# Power.net
KiCad netlist of a schematic drawn in Altium Designer
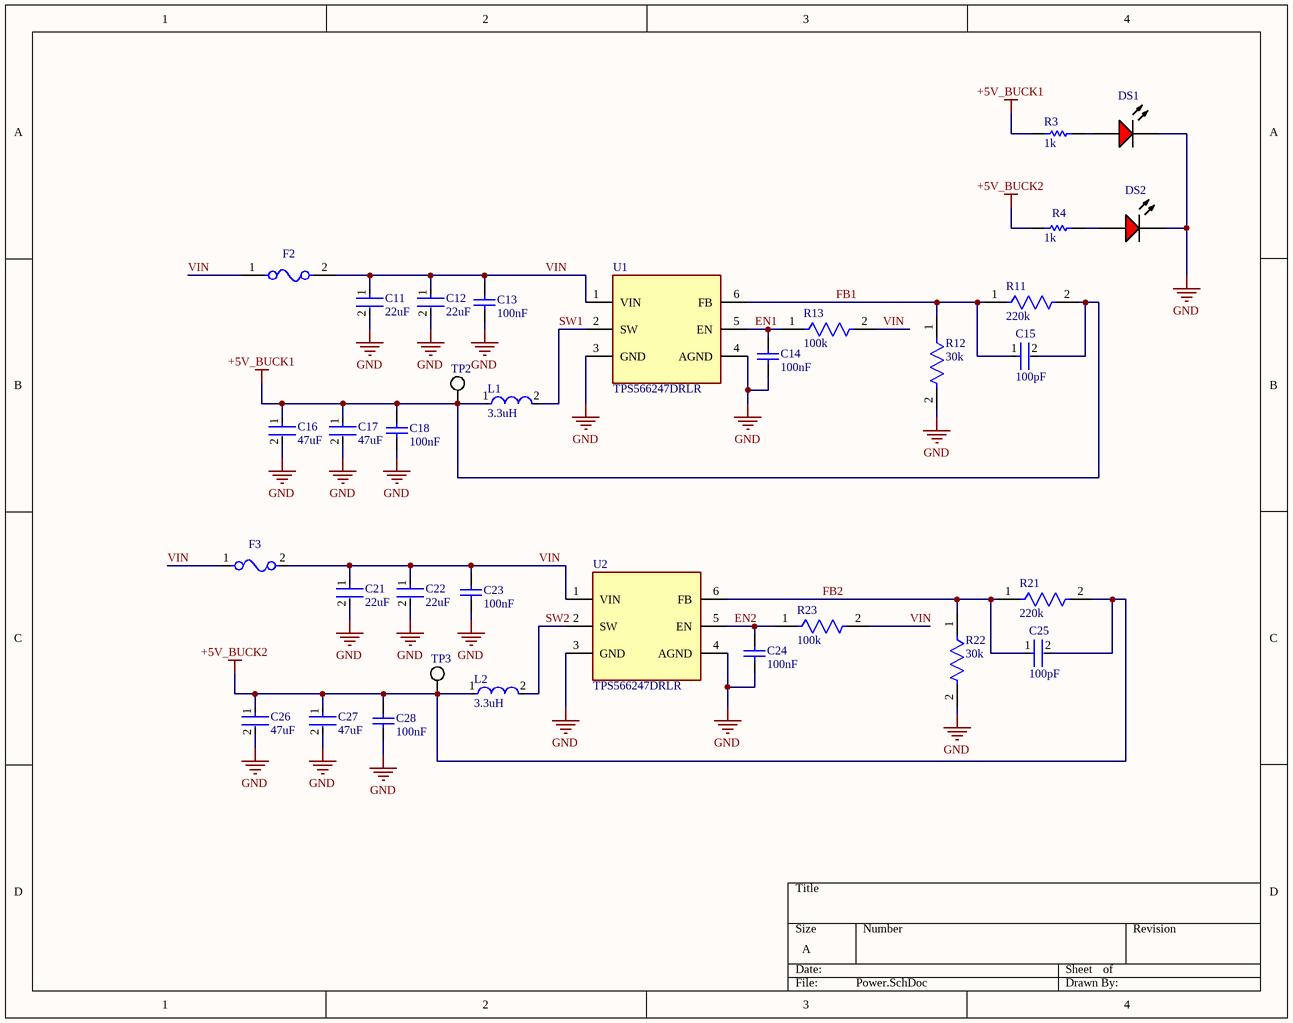
[diagram p0: Power.SchDoc]

(export (version "E")
  (design (tool "Eeschema 10.0.6"))
  (components
    (comp (ref "C11")
      (value "22uF")
      (footprint "FP-1206-L_3_2_0_3-W_1_6_0-IPC_A")
      (description "None")
      (fields (field (name "TOLERANCE") "20%"))
      (libsource (lib "Altium Content Vault") (part "11868f565c42a9108669ba33697ecf6"))
    )
    (comp (ref "C12")
      (value "22uF")
      (footprint "FP-1206-L_3_2_0_3-W_1_6_0-IPC_A")
      (description "None")
      (fields (field (name "TOLERANCE") "20%"))
      (libsource (lib "Altium Content Vault") (part "11868f565c42a9108669ba33697ecf6"))
    )
    (comp (ref "C13")
      (value "100nF")
      (footprint "CAPC1206(3216)170_L")
      (description "CAP 100nF 50V ±10% 1206 (3216 Metric) Thickness 1.7mm SMD")
      (fields (field (name "TOLERANCE") "Â±10%"))
      (libsource (lib "Altium Content Vault") (part "CAP"))
    )
    (comp (ref "C14")
      (value "100nF")
      (footprint "CAPC1206(3216)170_L")
      (description "CAP 100nF 50V ±10% 1206 (3216 Metric) Thickness 1.7mm SMD")
      (fields (field (name "TOLERANCE") "Â±10%"))
      (libsource (lib "Altium Content Vault") (part "CAP"))
    )
    (comp (ref "C15")
      (value "100pF")
      (footprint "FP-C0805C-DN-MFG")
      (description "CAP CER 100PF 50V 10% X7R 0805 (used for feed-forward)")
      (fields
        (field (name "OCTOPART") "https://octopart.com/c0805c101k5ractu-kemet-10441514")
        (field (name "MANUFACTURER") "KEMET")
      )
      (libsource (lib "Altium Content Vault") (part "b4654b650e69147ec39a6b967a45e02"))
    )
    (comp (ref "C16")
      (value "47uF")
      (footprint "FP-1210-L_3_2_0_3-W_2_5_0-IPC_B")
      (description "Capacitor Ceramic Multilayer 47uF 10% 10V X7R SMD 1210")
      (fields (field (name "TOLERANCE") "10%"))
      (libsource (lib "Altium Content Vault") (part "02cd4be3c70576c341d710602a673aa"))
    )
    (comp (ref "C17")
      (value "47uF")
      (footprint "FP-1210-L_3_2_0_3-W_2_5_0-IPC_B")
      (description "Capacitor Ceramic Multilayer 47uF 10% 10V X7R SMD 1210")
      (fields (field (name "TOLERANCE") "10%"))
      (libsource (lib "Altium Content Vault") (part "02cd4be3c70576c341d710602a673aa"))
    )
    (comp (ref "C18")
      (value "100nF")
      (footprint "CAPC1206(3216)170_L")
      (description "CAP 100nF 50V ±10% 1206 (3216 Metric) Thickness 1.7mm SMD")
      (fields (field (name "TOLERANCE") "Â±10%"))
      (libsource (lib "Altium Content Vault") (part "CAP"))
    )
    (comp (ref "C21")
      (value "22uF")
      (footprint "FP-1206-L_3_2_0_3-W_1_6_0-IPC_A")
      (description "None")
      (fields (field (name "TOLERANCE") "20%"))
      (libsource (lib "Altium Content Vault") (part "11868f565c42a9108669ba33697ecf6"))
    )
    (comp (ref "C22")
      (value "22uF")
      (footprint "FP-1206-L_3_2_0_3-W_1_6_0-IPC_A")
      (description "None")
      (fields (field (name "TOLERANCE") "20%"))
      (libsource (lib "Altium Content Vault") (part "11868f565c42a9108669ba33697ecf6"))
    )
    (comp (ref "C23")
      (value "100nF")
      (footprint "CAPC1206(3216)170_L")
      (description "CAP 100nF 50V ±10% 1206 (3216 Metric) Thickness 1.7mm SMD")
      (fields (field (name "TOLERANCE") "Â±10%"))
      (libsource (lib "Altium Content Vault") (part "CAP"))
    )
    (comp (ref "C24")
      (value "100nF")
      (footprint "CAPC1206(3216)170_L")
      (description "CAP 100nF 50V ±10% 1206 (3216 Metric) Thickness 1.7mm SMD")
      (fields (field (name "TOLERANCE") "Â±10%"))
      (libsource (lib "Altium Content Vault") (part "CAP"))
    )
    (comp (ref "C25")
      (value "100pF")
      (footprint "FP-C0805C-DN-MFG")
      (description "CAP CER 100PF 50V 10% X7R 0805 (used for feed-forward)")
      (fields
        (field (name "OCTOPART") "https://octopart.com/c0805c101k5ractu-kemet-10441514")
        (field (name "MANUFACTURER") "KEMET")
      )
      (libsource (lib "Altium Content Vault") (part "b4654b650e69147ec39a6b967a45e02"))
    )
    (comp (ref "C26")
      (value "47uF")
      (footprint "FP-1210-L_3_2_0_3-W_2_5_0-IPC_B")
      (description "Capacitor Ceramic Multilayer 47uF 10% 10V X7R SMD 1210")
      (fields (field (name "TOLERANCE") "10%"))
      (libsource (lib "Altium Content Vault") (part "02cd4be3c70576c341d710602a673aa"))
    )
    (comp (ref "C27")
      (value "47uF")
      (footprint "FP-1210-L_3_2_0_3-W_2_5_0-IPC_B")
      (description "Capacitor Ceramic Multilayer 47uF 10% 10V X7R SMD 1210")
      (fields (field (name "TOLERANCE") "10%"))
      (libsource (lib "Altium Content Vault") (part "02cd4be3c70576c341d710602a673aa"))
    )
    (comp (ref "C28")
      (value "100nF")
      (footprint "CAPC1206(3216)170_L")
      (description "CAP 100nF 50V ±10% 1206 (3216 Metric) Thickness 1.7mm SMD")
      (fields (field (name "TOLERANCE") "Â±10%"))
      (libsource (lib "Altium Content Vault") (part "CAP"))
    )
    (comp (ref "DS1")
      (value "SML-LX1206IC-TR")
      (footprint "LUMX-SML-LX1206IC_V")
      (description "LED Red, 65 mW, -40 to 85 degC, 2-Pin SMD, RoHS, Tape and Reel")
      (fields (field (name "MANUFACTURER") "Lumex"))
      (libsource (lib "Altium Content Vault") (part "LED-RED-AK-2"))
    )
    (comp (ref "DS2")
      (value "SML-LX1206IC-TR")
      (footprint "LUMX-SML-LX1206IC_V")
      (description "LED Red, 65 mW, -40 to 85 degC, 2-Pin SMD, RoHS, Tape and Reel")
      (fields (field (name "MANUFACTURER") "Lumex"))
      (libsource (lib "Altium Content Vault") (part "LED-RED-AK-2"))
    )
    (comp (ref "F2")
      (value "0466003.NR")
      (footprint "FP-0466-MFG")
      (description "FUSE BOARD MNT 3A 32VAC/VDC 1206")
      (fields
        (field (name "OCTOPART") "https://octopart.com/0466003.nr-littelfuse-565175")
        (field (name "MANUFACTURER") "Littelfuse")
      )
      (libsource (lib "Altium Content Vault") (part "5bcf9b9f640e542cf0359d10258e979"))
    )
    (comp (ref "F3")
      (value "ERB-RE2R00V")
      (footprint "FP-ERBRE-MFG")
      (description "ERB-RE2R00V Fuse Chip Fast Acting 2A 32V SMD Solder Pad 0603 1.6 X 0.8 X 0.54mm T/R UL/cUL")
      (libsource (lib "Altium Content Vault") (part "ERB-RE2R00V"))
    )
    (comp (ref "L1")
      (value "3.3uH")
      (footprint "FP-IHLP-4040DZ-FP_3_124x3-MFG")
      (description "Commercial Inductors, High Saturation Series 3.3uH 10A 14.4mΩ 20%")
      (fields (field (name "TOLERANCE") "20%"))
      (libsource (lib "Altium Content Vault") (part "725321dda6339637d4d059423bc1c3c"))
    )
    (comp (ref "L2")
      (value "3.3uH")
      (footprint "FP-IHLP-4040DZ-FP_3_124x3-MFG")
      (description "Commercial Inductors, High Saturation Series 3.3uH 10A 14.4mΩ 20%")
      (fields (field (name "TOLERANCE") "20%"))
      (libsource (lib "Altium Content Vault") (part "725321dda6339637d4d059423bc1c3c"))
    )
    (comp (ref "R3")
      (value "1k")
      (footprint "RESC3216X60X45ML10T20")
      (fields (field (name "MANUFACTURER") "Vishay Dale") (field (name "PART NUMBER") "CRCW12061K00JNTA"))
      (libsource (lib "Altium Content Vault") (part "RES"))
    )
    (comp (ref "R4")
      (value "1k")
      (footprint "RESC3216X60X45ML10T20")
      (fields (field (name "MANUFACTURER") "Vishay Dale") (field (name "PART NUMBER") "CRCW12061K00JNTA"))
      (libsource (lib "Altium Content Vault") (part "RES"))
    )
    (comp (ref "R11")
      (value "220k")
      (footprint "FP-CRGCQ1206-IPC_C")
      (description "CRGCQ1206 220KΩ 0.25W 1% ±100ppm/°C 200V")
      (fields
        (field (name "MANUFACTURER") "TE Connectivity")
        (field (name "OCTOPART") "https://octopart.com/crgcq1206f220k-te+connectivity-91018263")
      )
      (libsource (lib "Altium Content Vault") (part "1029c3af85768c4190bb7ad29bc67b5"))
    )
    (comp (ref "R12")
      (value "30k")
      (footprint "FP-MCU0805-MFG")
      (description "Thin Film Resistors - SMD MCU 0805-50 1% P5 30K")
      (fields (field (name "TOLERANCE") "1%"))
      (libsource (lib "Altium Content Vault") (part "1029c3af85768c4190bb7ad29bc67b5"))
    )
    (comp (ref "R13")
      (value "100k")
      (footprint "FP-RP732B-MFG")
      (description "Res Thin Film 1206 100KΩ 0.1% 0.25W 15ppm/°C Molded SMD")
      (fields
        (field (name "TOLERANCE") "0.1%")
        (field (name "OCTOPART") "https://octopart.com/rp73d2b100kbtg-te+connectivity-42012337")
      )
      (libsource (lib "Altium Content Vault") (part "1029c3af85768c4190bb7ad29bc67b5"))
    )
    (comp (ref "R21")
      (value "220k")
      (footprint "FP-CRGCQ1206-IPC_C")
      (description "CRGCQ1206 220KΩ 0.25W 1% ±100ppm/°C 200V")
      (fields
        (field (name "MANUFACTURER") "TE Connectivity")
        (field (name "OCTOPART") "https://octopart.com/crgcq1206f220k-te+connectivity-91018263")
      )
      (libsource (lib "Altium Content Vault") (part "1029c3af85768c4190bb7ad29bc67b5"))
    )
    (comp (ref "R22")
      (value "30k")
      (footprint "FP-MCU0805-MFG")
      (description "Thin Film Resistors - SMD MCU 0805-50 1% P5 30K")
      (fields (field (name "TOLERANCE") "1%"))
      (libsource (lib "Altium Content Vault") (part "1029c3af85768c4190bb7ad29bc67b5"))
    )
    (comp (ref "R23")
      (value "100k")
      (footprint "FP-RP732B-MFG")
      (description "Res Thin Film 1206 100KΩ 0.1% 0.25W 15ppm/°C Molded SMD")
      (fields
        (field (name "TOLERANCE") "0.1%")
        (field (name "OCTOPART") "https://octopart.com/rp73d2b100kbtg-te+connectivity-42012337")
      )
      (libsource (lib "Altium Content Vault") (part "1029c3af85768c4190bb7ad29bc67b5"))
    )
    (comp (ref "TP2")
      (value "Test Point")
      (footprint "Test Point")
      (libsource (lib "University of California, Riverside") (part "Test Point"))
    )
    (comp (ref "TP3")
      (value "Test Point")
      (footprint "Test Point")
      (libsource (lib "University of California, Riverside") (part "Test Point"))
    )
    (comp (ref "U1")
      (value "TPS566247DRLR")
      (footprint "SOTFL50P160X60-6N")
      (fields (field (name "MOUSER PART NUMBER") "595-TPS566247DRLR"))
      (libsource (lib "University of California, Riverside") (part "TPS566247DRLR"))
    )
    (comp (ref "U2")
      (value "TPS566247DRLR")
      (footprint "SOTFL50P160X60-6N")
      (fields (field (name "MOUSER PART NUMBER") "595-TPS566247DRLR"))
      (libsource (lib "University of California, Riverside") (part "TPS566247DRLR"))
    )
  )
  (nets
    (net (code "1") (name "+5V_BUCK1") (class "Default")
      (node (ref "C15") (pin "2") (pinfunction "2_2") (pintype "passive"))
      (node (ref "C16") (pin "1") (pinfunction "1_1") (pintype "passive"))
      (node (ref "C17") (pin "1") (pinfunction "1_1") (pintype "passive"))
      (node (ref "C18") (pin "2") (pinfunction "2_2") (pintype "passive"))
      (node (ref "L1") (pin "1") (pinfunction "1_1") (pintype "passive"))
      (node (ref "R11") (pin "2") (pinfunction "2_2") (pintype "passive"))
      (node (ref "R3") (pin "1") (pinfunction "1_1") (pintype "passive"))
      (node (ref "TP2") (pin "1") (pinfunction "1_1") (pintype "passive"))
    )
    (net (code "2") (name "+5V_BUCK2") (class "Default")
      (node (ref "C25") (pin "2") (pinfunction "2_2") (pintype "passive"))
      (node (ref "C26") (pin "1") (pinfunction "1_1") (pintype "passive"))
      (node (ref "C27") (pin "1") (pinfunction "1_1") (pintype "passive"))
      (node (ref "C28") (pin "2") (pinfunction "2_2") (pintype "passive"))
      (node (ref "L2") (pin "1") (pinfunction "1_1") (pintype "passive"))
      (node (ref "R21") (pin "2") (pinfunction "2_2") (pintype "passive"))
      (node (ref "R4") (pin "1") (pinfunction "1_1") (pintype "passive"))
      (node (ref "TP3") (pin "1") (pinfunction "1_1") (pintype "passive"))
    )
    (net (code "3") (name "/EN1") (class "Default")
      (node (ref "C14") (pin "2") (pinfunction "2_2") (pintype "passive"))
      (node (ref "R13") (pin "1") (pinfunction "1_1") (pintype "passive"))
      (node (ref "U1") (pin "5") (pinfunction "EN_5") (pintype "passive"))
    )
    (net (code "4") (name "/EN2") (class "Default")
      (node (ref "C24") (pin "2") (pinfunction "2_2") (pintype "passive"))
      (node (ref "R23") (pin "1") (pinfunction "1_1") (pintype "passive"))
      (node (ref "U2") (pin "5") (pinfunction "EN_5") (pintype "passive"))
    )
    (net (code "5") (name "/FB1") (class "Default")
      (node (ref "C15") (pin "1") (pinfunction "1_1") (pintype "passive"))
      (node (ref "R11") (pin "1") (pinfunction "1_1") (pintype "passive"))
      (node (ref "R12") (pin "1") (pinfunction "1_1") (pintype "passive"))
      (node (ref "U1") (pin "6") (pinfunction "FB_6") (pintype "passive"))
    )
    (net (code "6") (name "/FB2") (class "Default")
      (node (ref "C25") (pin "1") (pinfunction "1_1") (pintype "passive"))
      (node (ref "R21") (pin "1") (pinfunction "1_1") (pintype "passive"))
      (node (ref "R22") (pin "1") (pinfunction "1_1") (pintype "passive"))
      (node (ref "U2") (pin "6") (pinfunction "FB_6") (pintype "passive"))
    )
    (net (code "7") (name "/SW1") (class "Default")
      (node (ref "L1") (pin "2") (pinfunction "2_2") (pintype "passive"))
      (node (ref "U1") (pin "2") (pinfunction "SW_2") (pintype "passive"))
    )
    (net (code "8") (name "/SW2") (class "Default")
      (node (ref "L2") (pin "2") (pinfunction "2_2") (pintype "passive"))
      (node (ref "U2") (pin "2") (pinfunction "SW_2") (pintype "passive"))
    )
    (net (code "9") (name "/VIN") (class "Default")
      (node (ref "C11") (pin "1") (pinfunction "1_1") (pintype "passive"))
      (node (ref "C12") (pin "1") (pinfunction "1_1") (pintype "passive"))
      (node (ref "C13") (pin "2") (pinfunction "2_2") (pintype "passive"))
      (node (ref "C21") (pin "1") (pinfunction "1_1") (pintype "passive"))
      (node (ref "C22") (pin "1") (pinfunction "1_1") (pintype "passive"))
      (node (ref "C23") (pin "2") (pinfunction "2_2") (pintype "passive"))
      (node (ref "F2") (pin "1") (pinfunction "1_1") (pintype "passive"))
      (node (ref "F2") (pin "2") (pinfunction "2_2") (pintype "passive"))
      (node (ref "F3") (pin "1") (pinfunction "1_1") (pintype "passive"))
      (node (ref "F3") (pin "2") (pinfunction "2_2") (pintype "passive"))
      (node (ref "R13") (pin "2") (pinfunction "2_2") (pintype "passive"))
      (node (ref "R23") (pin "2") (pinfunction "2_2") (pintype "passive"))
      (node (ref "U1") (pin "1") (pinfunction "VIN_1") (pintype "passive"))
      (node (ref "U2") (pin "1") (pinfunction "VIN_1") (pintype "passive"))
    )
    (net (code "10") (name "GND") (class "Default")
      (node (ref "C11") (pin "2") (pinfunction "2_2") (pintype "passive"))
      (node (ref "C12") (pin "2") (pinfunction "2_2") (pintype "passive"))
      (node (ref "C13") (pin "1") (pinfunction "1_1") (pintype "passive"))
      (node (ref "C14") (pin "1") (pinfunction "1_1") (pintype "passive"))
      (node (ref "C16") (pin "2") (pinfunction "2_2") (pintype "passive"))
      (node (ref "C17") (pin "2") (pinfunction "2_2") (pintype "passive"))
      (node (ref "C18") (pin "1") (pinfunction "1_1") (pintype "passive"))
      (node (ref "C21") (pin "2") (pinfunction "2_2") (pintype "passive"))
      (node (ref "C22") (pin "2") (pinfunction "2_2") (pintype "passive"))
      (node (ref "C23") (pin "1") (pinfunction "1_1") (pintype "passive"))
      (node (ref "C24") (pin "1") (pinfunction "1_1") (pintype "passive"))
      (node (ref "C26") (pin "2") (pinfunction "2_2") (pintype "passive"))
      (node (ref "C27") (pin "2") (pinfunction "2_2") (pintype "passive"))
      (node (ref "C28") (pin "1") (pinfunction "1_1") (pintype "passive"))
      (node (ref "DS1") (pin "2") (pinfunction "K_2") (pintype "passive"))
      (node (ref "DS2") (pin "2") (pinfunction "K_2") (pintype "passive"))
      (node (ref "R12") (pin "2") (pinfunction "2_2") (pintype "passive"))
      (node (ref "R22") (pin "2") (pinfunction "2_2") (pintype "passive"))
      (node (ref "U1") (pin "3") (pinfunction "GND_3") (pintype "passive"))
      (node (ref "U1") (pin "4") (pinfunction "AGND_4") (pintype "passive"))
      (node (ref "U2") (pin "3") (pinfunction "GND_3") (pintype "passive"))
      (node (ref "U2") (pin "4") (pinfunction "AGND_4") (pintype "passive"))
    )
    (net (code "11") (name "Net-(DS1-A)") (class "Default")
      (node (ref "DS1") (pin "1") (pinfunction "A_1") (pintype "passive"))
      (node (ref "R3") (pin "2") (pinfunction "2_2") (pintype "passive"))
    )
    (net (code "12") (name "Net-(DS2-A)") (class "Default")
      (node (ref "DS2") (pin "1") (pinfunction "A_1") (pintype "passive"))
      (node (ref "R4") (pin "2") (pinfunction "2_2") (pintype "passive"))
    )
  )
)
